# SCH_M5_Stick_BrownHat_2022-11-10.net
KiCad netlist of a schematic drawn in EasyEDA
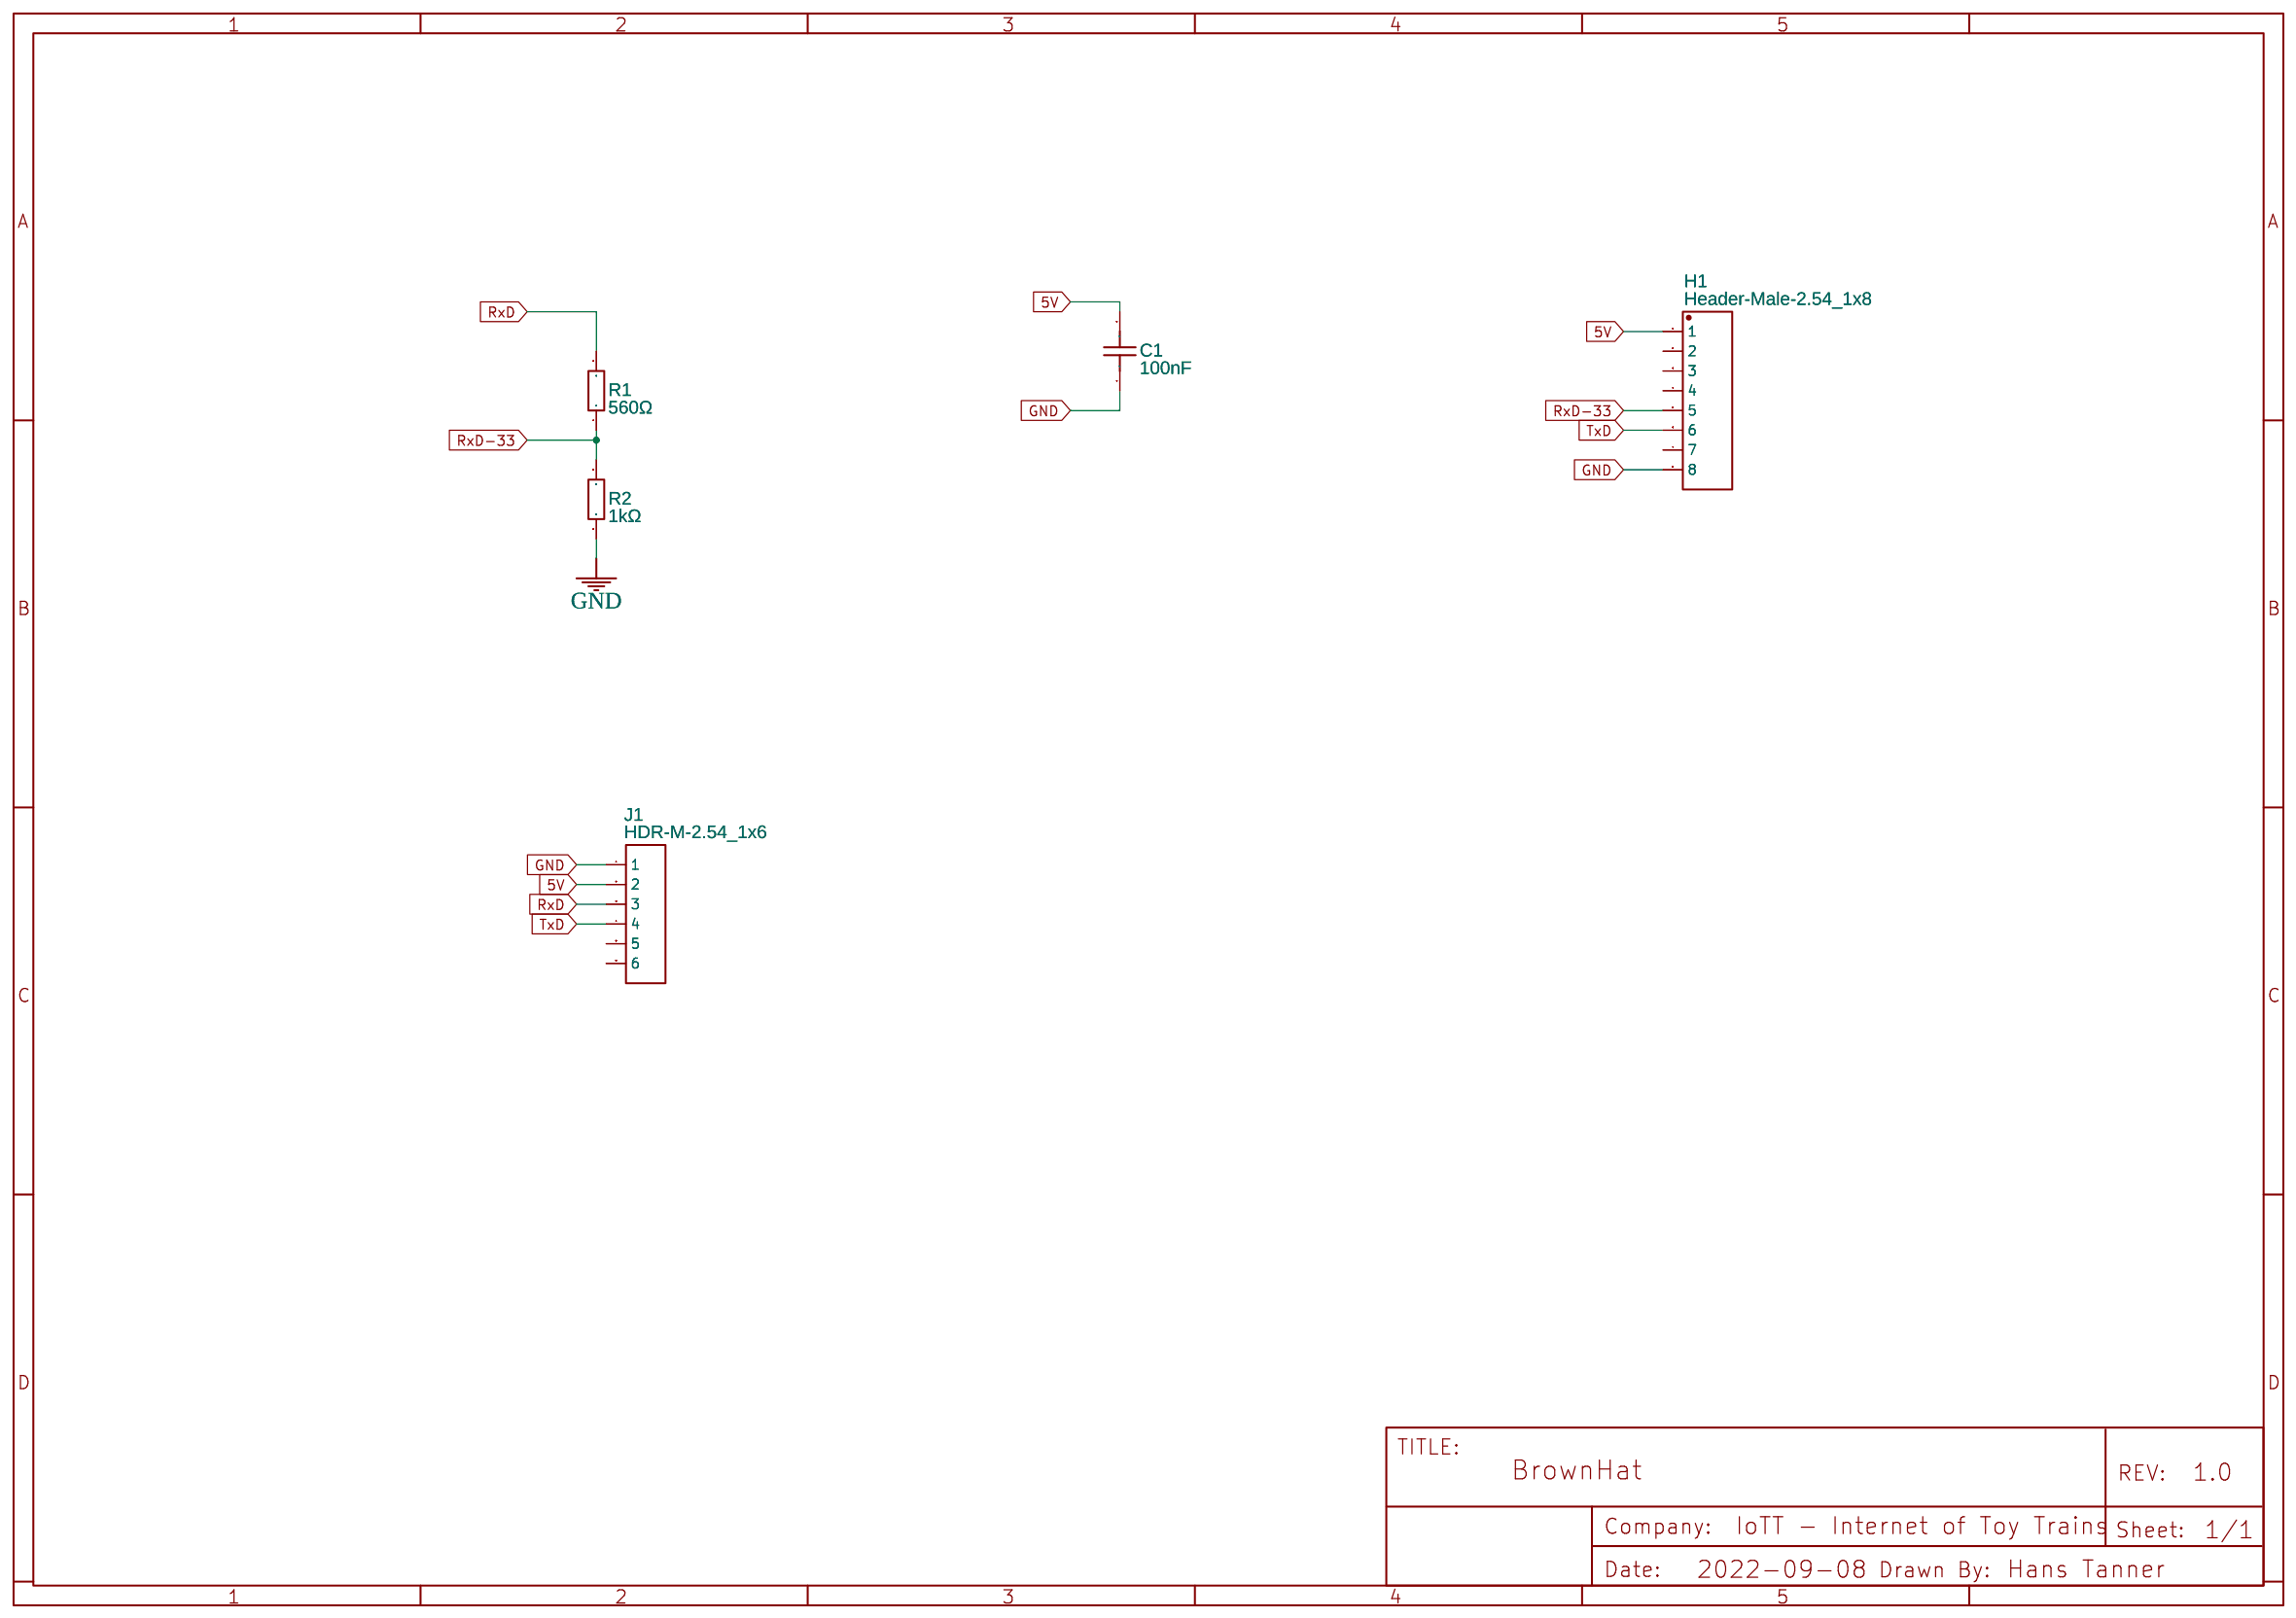
[diagram p0: schematic sheet]

(export (version "E")
  (design (tool "Eeschema 10.0.6"))
  (components
    (comp (ref "C1")
      (value "100nF")
      (fields
        (field (name "BOM_Manufacturer Part") "CC0603KRX7R9BB104")
        (field (name "BOM_Supplier Part") "C14663")
      )
      (libsource (lib "") (part "CC0603KRX7R9BB104"))
    )
    (comp (ref "H1")
      (value "Header-Male-2.54_1x8")
      (fields
        (field (name "BOM_Manufacturer Part") "210S-1*8P L=11.6MMGold-plated black")
        (field (name "BOM_Supplier Part") "C124381")
      )
      (libsource (lib "") (part "Header-Male-2.54_1x8"))
    )
    (comp (ref "J1")
      (value "HDR-M-2.54_1x6")
      (fields (field (name "BOM_Supplier Part") "C190819"))
      (libsource (lib "") (part "HDR-M-2.54_1x6"))
    )
    (comp (ref "R1")
      (value "560Ω")
      (fields
        (field (name "BOM_Manufacturer Part") "0603WAF5600T5E")
        (field (name "BOM_Supplier Part") "C23204")
      )
      (libsource (lib "") (part "0603WAF5600T5E"))
    )
    (comp (ref "R2")
      (value "1kΩ")
      (fields
        (field (name "BOM_Manufacturer Part") "0402WGF1001TCE")
        (field (name "BOM_Supplier Part") "C11702")
      )
      (libsource (lib "") (part "0402WGF1001TCE"))
    )
  )
  (nets
    (net (code "1") (name "5V") (class "Default")
      (node (ref "C1") (pin "2") (pinfunction "2_2") (pintype "unspecified"))
      (node (ref "H1") (pin "1") (pinfunction "1_1") (pintype "unspecified"))
      (node (ref "J1") (pin "2") (pinfunction "2_2") (pintype "input"))
    )
    (net (code "2") (name "GND") (class "Default")
      (node (ref "C1") (pin "1") (pinfunction "1_1") (pintype "unspecified"))
      (node (ref "H1") (pin "8") (pinfunction "8_8") (pintype "unspecified"))
      (node (ref "J1") (pin "1") (pinfunction "1_1") (pintype "input"))
      (node (ref "R2") (pin "1") (pinfunction "1_1") (pintype "input"))
    )
    (net (code "3") (name "RxD") (class "Default")
      (node (ref "J1") (pin "3") (pinfunction "3_3") (pintype "input"))
      (node (ref "R1") (pin "2") (pinfunction "2_2") (pintype "input"))
    )
    (net (code "4") (name "RxD-33") (class "Default")
      (node (ref "H1") (pin "5") (pinfunction "5_5") (pintype "unspecified"))
      (node (ref "R1") (pin "1") (pinfunction "1_1") (pintype "input"))
      (node (ref "R2") (pin "2") (pinfunction "2_2") (pintype "input"))
    )
    (net (code "5") (name "TxD") (class "Default")
      (node (ref "H1") (pin "6") (pinfunction "6_6") (pintype "unspecified"))
      (node (ref "J1") (pin "4") (pinfunction "4_4") (pintype "input"))
    )
    (net (code "6") (name "unconnected-(H1-Pad2)") (class "Default")
      (node (ref "H1") (pin "2") (pinfunction "2_2") (pintype "unspecified"))
    )
    (net (code "7") (name "unconnected-(H1-Pad3)") (class "Default")
      (node (ref "H1") (pin "3") (pinfunction "3_3") (pintype "unspecified"))
    )
    (net (code "8") (name "unconnected-(H1-Pad4)") (class "Default")
      (node (ref "H1") (pin "4") (pinfunction "4_4") (pintype "unspecified"))
    )
    (net (code "9") (name "unconnected-(H1-Pad7)") (class "Default")
      (node (ref "H1") (pin "7") (pinfunction "7_7") (pintype "unspecified"))
    )
    (net (code "10") (name "unconnected-(J1-Pad5)") (class "Default")
      (node (ref "J1") (pin "5") (pinfunction "5_5") (pintype "input"))
    )
    (net (code "11") (name "unconnected-(J1-Pad6)") (class "Default")
      (node (ref "J1") (pin "6") (pinfunction "6_6") (pintype "input"))
    )
  )
)
